# ExternalIO.net
KiCad netlist of a schematic drawn in Altium Designer
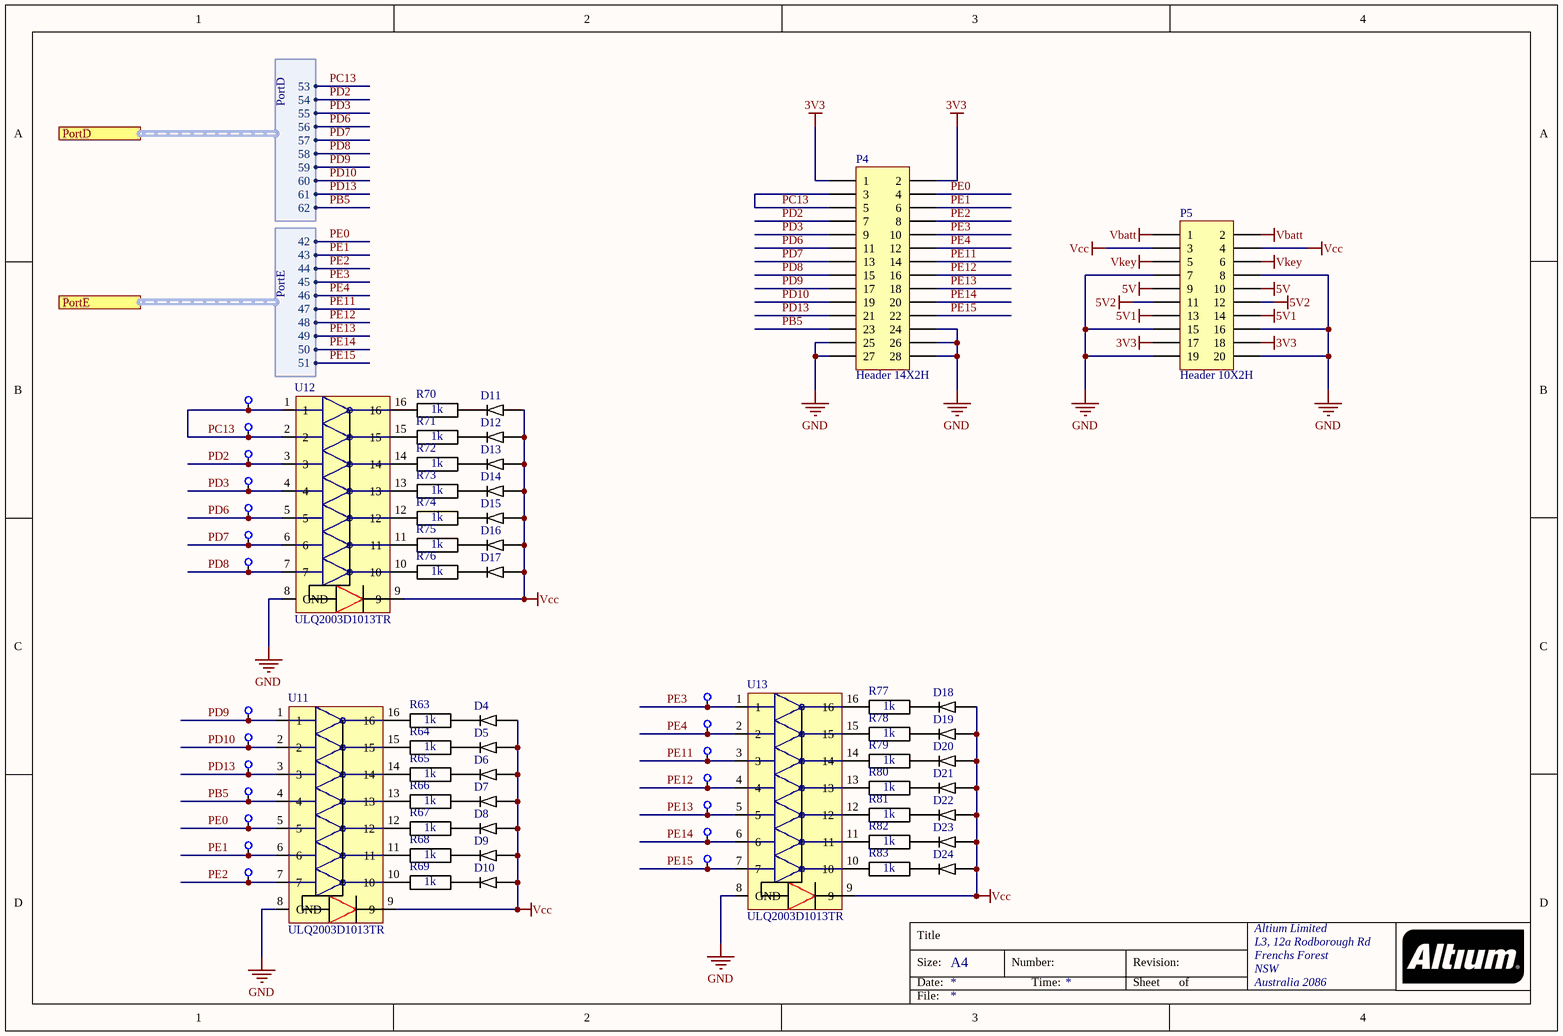
[diagram p0: ExternalIO.SchDoc]

(export (version "E")
  (design (tool "Eeschema 10.0.6"))
  (components
    (comp (ref "D4")
      (value "LED")
      (footprint "LED 0805")
      (description "LTST-C171GKT")
      (libsource (lib "Maks_lib") (part "LED"))
    )
    (comp (ref "D5")
      (value "LED")
      (footprint "LED 0805")
      (description "LTST-C171GKT")
      (libsource (lib "Maks_lib") (part "LED"))
    )
    (comp (ref "D6")
      (value "LED")
      (footprint "LED 0805")
      (description "LTST-C171GKT")
      (libsource (lib "Maks_lib") (part "LED"))
    )
    (comp (ref "D7")
      (value "LED")
      (footprint "LED 0805")
      (description "LTST-C171GKT")
      (libsource (lib "Maks_lib") (part "LED"))
    )
    (comp (ref "D8")
      (value "LED")
      (footprint "LED 0805")
      (description "LTST-C171GKT")
      (libsource (lib "Maks_lib") (part "LED"))
    )
    (comp (ref "D9")
      (value "LED")
      (footprint "LED 0805")
      (description "LTST-C171GKT")
      (libsource (lib "Maks_lib") (part "LED"))
    )
    (comp (ref "D10")
      (value "LED")
      (footprint "LED 0805")
      (description "LTST-C171GKT")
      (libsource (lib "Maks_lib") (part "LED"))
    )
    (comp (ref "D11")
      (value "LED")
      (footprint "LED 0805")
      (description "LTST-C171GKT")
      (libsource (lib "Maks_lib") (part "LED"))
    )
    (comp (ref "D12")
      (value "LED")
      (footprint "LED 0805")
      (description "LTST-C171GKT")
      (libsource (lib "Maks_lib") (part "LED"))
    )
    (comp (ref "D13")
      (value "LED")
      (footprint "LED 0805")
      (description "LTST-C171GKT")
      (libsource (lib "Maks_lib") (part "LED"))
    )
    (comp (ref "D14")
      (value "LED")
      (footprint "LED 0805")
      (description "LTST-C171GKT")
      (libsource (lib "Maks_lib") (part "LED"))
    )
    (comp (ref "D15")
      (value "LED")
      (footprint "LED 0805")
      (description "LTST-C171GKT")
      (libsource (lib "Maks_lib") (part "LED"))
    )
    (comp (ref "D16")
      (value "LED")
      (footprint "LED 0805")
      (description "LTST-C171GKT")
      (libsource (lib "Maks_lib") (part "LED"))
    )
    (comp (ref "D17")
      (value "LED")
      (footprint "LED 0805")
      (description "LTST-C171GKT")
      (libsource (lib "Maks_lib") (part "LED"))
    )
    (comp (ref "D18")
      (value "LED")
      (footprint "LED 0805")
      (description "LTST-C171GKT")
      (libsource (lib "Maks_lib") (part "LED"))
    )
    (comp (ref "D19")
      (value "LED")
      (footprint "LED 0805")
      (description "LTST-C171GKT")
      (libsource (lib "Maks_lib") (part "LED"))
    )
    (comp (ref "D20")
      (value "LED")
      (footprint "LED 0805")
      (description "LTST-C171GKT")
      (libsource (lib "Maks_lib") (part "LED"))
    )
    (comp (ref "D21")
      (value "LED")
      (footprint "LED 0805")
      (description "LTST-C171GKT")
      (libsource (lib "Maks_lib") (part "LED"))
    )
    (comp (ref "D22")
      (value "LED")
      (footprint "LED 0805")
      (description "LTST-C171GKT")
      (libsource (lib "Maks_lib") (part "LED"))
    )
    (comp (ref "D23")
      (value "LED")
      (footprint "LED 0805")
      (description "LTST-C171GKT")
      (libsource (lib "Maks_lib") (part "LED"))
    )
    (comp (ref "D24")
      (value "LED")
      (footprint "LED 0805")
      (description "LTST-C171GKT")
      (libsource (lib "Maks_lib") (part "LED"))
    )
    (comp (ref "P4")
      (value "Header 14X2H")
      (footprint "HDR2X14H")
      (description "Header, 14-Pin, Dual row, Right Angle")
      (fields (field (name "PUBLISHER") "Altium Limited"))
      (libsource (lib "Miscellaneous Connectors") (part "Header 14X2H"))
    )
    (comp (ref "P5")
      (value "Header 10X2H")
      (footprint "HDR2X10H")
      (description "Header, 10-Pin, Dual row, Right Angle")
      (fields (field (name "PUBLISHER") "Altium Limited"))
      (libsource (lib "Miscellaneous Connectors") (part "Header 10X2H"))
    )
    (comp (ref "R63")
      (value "1k")
      (footprint "SMD 0805")
      (description "RC0805FR-071KL")
      (libsource (lib "Maks_lib") (part "Resistor"))
    )
    (comp (ref "R64")
      (value "1k")
      (footprint "SMD 0805")
      (description "RC0805FR-071KL")
      (libsource (lib "Maks_lib") (part "Resistor"))
    )
    (comp (ref "R65")
      (value "1k")
      (footprint "SMD 0805")
      (description "RC0805FR-071KL")
      (libsource (lib "Maks_lib") (part "Resistor"))
    )
    (comp (ref "R66")
      (value "1k")
      (footprint "SMD 0805")
      (description "RC0805FR-071KL")
      (libsource (lib "Maks_lib") (part "Resistor"))
    )
    (comp (ref "R67")
      (value "1k")
      (footprint "SMD 0805")
      (description "RC0805FR-071KL")
      (libsource (lib "Maks_lib") (part "Resistor"))
    )
    (comp (ref "R68")
      (value "1k")
      (footprint "SMD 0805")
      (description "RC0805FR-071KL")
      (libsource (lib "Maks_lib") (part "Resistor"))
    )
    (comp (ref "R69")
      (value "1k")
      (footprint "SMD 0805")
      (description "RC0805FR-071KL")
      (libsource (lib "Maks_lib") (part "Resistor"))
    )
    (comp (ref "R70")
      (value "1k")
      (footprint "SMD 0805")
      (description "RC0805FR-071KL")
      (libsource (lib "Maks_lib") (part "Resistor"))
    )
    (comp (ref "R71")
      (value "1k")
      (footprint "SMD 0805")
      (description "RC0805FR-071KL")
      (libsource (lib "Maks_lib") (part "Resistor"))
    )
    (comp (ref "R72")
      (value "1k")
      (footprint "SMD 0805")
      (description "RC0805FR-071KL")
      (libsource (lib "Maks_lib") (part "Resistor"))
    )
    (comp (ref "R73")
      (value "1k")
      (footprint "SMD 0805")
      (description "RC0805FR-071KL")
      (libsource (lib "Maks_lib") (part "Resistor"))
    )
    (comp (ref "R74")
      (value "1k")
      (footprint "SMD 0805")
      (description "RC0805FR-071KL")
      (libsource (lib "Maks_lib") (part "Resistor"))
    )
    (comp (ref "R75")
      (value "1k")
      (footprint "SMD 0805")
      (description "RC0805FR-071KL")
      (libsource (lib "Maks_lib") (part "Resistor"))
    )
    (comp (ref "R76")
      (value "1k")
      (footprint "SMD 0805")
      (description "RC0805FR-071KL")
      (libsource (lib "Maks_lib") (part "Resistor"))
    )
    (comp (ref "R77")
      (value "1k")
      (footprint "SMD 0805")
      (description "RC0805FR-071KL")
      (libsource (lib "Maks_lib") (part "Resistor"))
    )
    (comp (ref "R78")
      (value "1k")
      (footprint "SMD 0805")
      (description "RC0805FR-071KL")
      (libsource (lib "Maks_lib") (part "Resistor"))
    )
    (comp (ref "R79")
      (value "1k")
      (footprint "SMD 0805")
      (description "RC0805FR-071KL")
      (libsource (lib "Maks_lib") (part "Resistor"))
    )
    (comp (ref "R80")
      (value "1k")
      (footprint "SMD 0805")
      (description "RC0805FR-071KL")
      (libsource (lib "Maks_lib") (part "Resistor"))
    )
    (comp (ref "R81")
      (value "1k")
      (footprint "SMD 0805")
      (description "RC0805FR-071KL")
      (libsource (lib "Maks_lib") (part "Resistor"))
    )
    (comp (ref "R82")
      (value "1k")
      (footprint "SMD 0805")
      (description "RC0805FR-071KL")
      (libsource (lib "Maks_lib") (part "Resistor"))
    )
    (comp (ref "R83")
      (value "1k")
      (footprint "SMD 0805")
      (description "RC0805FR-071KL")
      (libsource (lib "Maks_lib") (part "Resistor"))
    )
    (comp (ref "TP69")
      (value "TestPoint")
      (footprint "TESTPOINT")
      (description "testPoint")
      (libsource (lib "Maks_lib") (part "TestPoint"))
    )
    (comp (ref "TP70")
      (value "TestPoint")
      (footprint "TESTPOINT")
      (description "testPoint")
      (libsource (lib "Maks_lib") (part "TestPoint"))
    )
    (comp (ref "TP71")
      (value "TestPoint")
      (footprint "TESTPOINT")
      (description "testPoint")
      (libsource (lib "Maks_lib") (part "TestPoint"))
    )
    (comp (ref "TP72")
      (value "TestPoint")
      (footprint "TESTPOINT")
      (description "testPoint")
      (libsource (lib "Maks_lib") (part "TestPoint"))
    )
    (comp (ref "TP73")
      (value "TestPoint")
      (footprint "TESTPOINT")
      (description "testPoint")
      (libsource (lib "Maks_lib") (part "TestPoint"))
    )
    (comp (ref "TP74")
      (value "TestPoint")
      (footprint "TESTPOINT")
      (description "testPoint")
      (libsource (lib "Maks_lib") (part "TestPoint"))
    )
    (comp (ref "TP75")
      (value "TestPoint")
      (footprint "TESTPOINT")
      (description "testPoint")
      (libsource (lib "Maks_lib") (part "TestPoint"))
    )
    (comp (ref "TP76")
      (value "TestPoint")
      (footprint "TESTPOINT")
      (description "testPoint")
      (libsource (lib "Maks_lib") (part "TestPoint"))
    )
    (comp (ref "TP77")
      (value "TestPoint")
      (footprint "TESTPOINT")
      (description "testPoint")
      (libsource (lib "Maks_lib") (part "TestPoint"))
    )
    (comp (ref "TP78")
      (value "TestPoint")
      (footprint "TESTPOINT")
      (description "testPoint")
      (libsource (lib "Maks_lib") (part "TestPoint"))
    )
    (comp (ref "TP79")
      (value "TestPoint")
      (footprint "TESTPOINT")
      (description "testPoint")
      (libsource (lib "Maks_lib") (part "TestPoint"))
    )
    (comp (ref "TP80")
      (value "TestPoint")
      (footprint "TESTPOINT")
      (description "testPoint")
      (libsource (lib "Maks_lib") (part "TestPoint"))
    )
    (comp (ref "TP81")
      (value "TestPoint")
      (footprint "TESTPOINT")
      (description "testPoint")
      (libsource (lib "Maks_lib") (part "TestPoint"))
    )
    (comp (ref "TP82")
      (value "TestPoint")
      (footprint "TESTPOINT")
      (description "testPoint")
      (libsource (lib "Maks_lib") (part "TestPoint"))
    )
    (comp (ref "TP83")
      (value "TestPoint")
      (footprint "TESTPOINT")
      (description "testPoint")
      (libsource (lib "Maks_lib") (part "TestPoint"))
    )
    (comp (ref "TP84")
      (value "TestPoint")
      (footprint "TESTPOINT")
      (description "testPoint")
      (libsource (lib "Maks_lib") (part "TestPoint"))
    )
    (comp (ref "TP85")
      (value "TestPoint")
      (footprint "TESTPOINT")
      (description "testPoint")
      (libsource (lib "Maks_lib") (part "TestPoint"))
    )
    (comp (ref "TP86")
      (value "TestPoint")
      (footprint "TESTPOINT")
      (description "testPoint")
      (libsource (lib "Maks_lib") (part "TestPoint"))
    )
    (comp (ref "TP87")
      (value "TestPoint")
      (footprint "TESTPOINT")
      (description "testPoint")
      (libsource (lib "Maks_lib") (part "TestPoint"))
    )
    (comp (ref "TP88")
      (value "TestPoint")
      (footprint "TESTPOINT")
      (description "testPoint")
      (libsource (lib "Maks_lib") (part "TestPoint"))
    )
    (comp (ref "TP89")
      (value "TestPoint")
      (footprint "TESTPOINT")
      (description "testPoint")
      (libsource (lib "Maks_lib") (part "TestPoint"))
    )
    (comp (ref "U11")
      (value "ULQ2003D1013TR")
      (footprint "SOIC127P600X175_HS-17M")
      (libsource (lib "Maks_lib") (part "ULN2003AIDR"))
    )
    (comp (ref "U12")
      (value "ULQ2003D1013TR")
      (footprint "SOIC127P600X175_HS-17M")
      (libsource (lib "Maks_lib") (part "ULN2003AIDR"))
    )
    (comp (ref "U13")
      (value "ULQ2003D1013TR")
      (footprint "SOIC127P600X175_HS-17M")
      (libsource (lib "Maks_lib") (part "ULN2003AIDR"))
    )
  )
  (nets
    (net (code "3") (name "/PB5") (class "Default")
      (node (ref "P4") (pin "23") (pinfunction "23_23") (pintype "passive"))
      (node (ref "TP79") (pin "0") (pinfunction "0_0") (pintype "passive"))
      (node (ref "U11") (pin "4") (pinfunction "4_4") (pintype "passive"))
    )
    (net (code "4") (name "/PC13") (class "Default")
      (node (ref "P4") (pin "3") (pinfunction "3_3") (pintype "passive"))
      (node (ref "P4") (pin "5") (pinfunction "5_5") (pintype "passive"))
      (node (ref "TP69") (pin "0") (pinfunction "0_0") (pintype "passive"))
      (node (ref "TP70") (pin "0") (pinfunction "0_0") (pintype "passive"))
      (node (ref "U12") (pin "1") (pinfunction "1_1") (pintype "passive"))
      (node (ref "U12") (pin "2") (pinfunction "2_2") (pintype "passive"))
    )
    (net (code "5") (name "/PD2") (class "Default")
      (node (ref "P4") (pin "7") (pinfunction "7_7") (pintype "passive"))
      (node (ref "TP71") (pin "0") (pinfunction "0_0") (pintype "passive"))
      (node (ref "U12") (pin "3") (pinfunction "3_3") (pintype "passive"))
    )
    (net (code "6") (name "/PD3") (class "Default")
      (node (ref "P4") (pin "9") (pinfunction "9_9") (pintype "passive"))
      (node (ref "TP72") (pin "0") (pinfunction "0_0") (pintype "passive"))
      (node (ref "U12") (pin "4") (pinfunction "4_4") (pintype "passive"))
    )
    (net (code "7") (name "/PD6") (class "Default")
      (node (ref "P4") (pin "11") (pinfunction "11_11") (pintype "passive"))
      (node (ref "TP73") (pin "0") (pinfunction "0_0") (pintype "passive"))
      (node (ref "U12") (pin "5") (pinfunction "5_5") (pintype "passive"))
    )
    (net (code "8") (name "/PD7") (class "Default")
      (node (ref "P4") (pin "13") (pinfunction "13_13") (pintype "passive"))
      (node (ref "TP74") (pin "0") (pinfunction "0_0") (pintype "passive"))
      (node (ref "U12") (pin "6") (pinfunction "6_6") (pintype "passive"))
    )
    (net (code "9") (name "/PD8") (class "Default")
      (node (ref "P4") (pin "15") (pinfunction "15_15") (pintype "passive"))
      (node (ref "TP75") (pin "0") (pinfunction "0_0") (pintype "passive"))
      (node (ref "U12") (pin "7") (pinfunction "7_7") (pintype "passive"))
    )
    (net (code "10") (name "/PD9") (class "Default")
      (node (ref "P4") (pin "17") (pinfunction "17_17") (pintype "passive"))
      (node (ref "TP76") (pin "0") (pinfunction "0_0") (pintype "passive"))
      (node (ref "U11") (pin "1") (pinfunction "1_1") (pintype "passive"))
    )
    (net (code "11") (name "/PD10") (class "Default")
      (node (ref "P4") (pin "19") (pinfunction "19_19") (pintype "passive"))
      (node (ref "TP77") (pin "0") (pinfunction "0_0") (pintype "passive"))
      (node (ref "U11") (pin "2") (pinfunction "2_2") (pintype "passive"))
    )
    (net (code "12") (name "/PD13") (class "Default")
      (node (ref "P4") (pin "21") (pinfunction "21_21") (pintype "passive"))
      (node (ref "TP78") (pin "0") (pinfunction "0_0") (pintype "passive"))
      (node (ref "U11") (pin "3") (pinfunction "3_3") (pintype "passive"))
    )
    (net (code "13") (name "/PE0") (class "Default")
      (node (ref "P4") (pin "4") (pinfunction "4_4") (pintype "passive"))
      (node (ref "TP80") (pin "0") (pinfunction "0_0") (pintype "passive"))
      (node (ref "U11") (pin "5") (pinfunction "5_5") (pintype "passive"))
    )
    (net (code "14") (name "/PE1") (class "Default")
      (node (ref "P4") (pin "6") (pinfunction "6_6") (pintype "passive"))
      (node (ref "TP81") (pin "0") (pinfunction "0_0") (pintype "passive"))
      (node (ref "U11") (pin "6") (pinfunction "6_6") (pintype "passive"))
    )
    (net (code "15") (name "/PE2") (class "Default")
      (node (ref "P4") (pin "8") (pinfunction "8_8") (pintype "passive"))
      (node (ref "TP82") (pin "0") (pinfunction "0_0") (pintype "passive"))
      (node (ref "U11") (pin "7") (pinfunction "7_7") (pintype "passive"))
    )
    (net (code "16") (name "/PE3") (class "Default")
      (node (ref "P4") (pin "10") (pinfunction "10_10") (pintype "passive"))
      (node (ref "TP83") (pin "0") (pinfunction "0_0") (pintype "passive"))
      (node (ref "U13") (pin "1") (pinfunction "1_1") (pintype "passive"))
    )
    (net (code "17") (name "/PE4") (class "Default")
      (node (ref "P4") (pin "12") (pinfunction "12_12") (pintype "passive"))
      (node (ref "TP84") (pin "0") (pinfunction "0_0") (pintype "passive"))
      (node (ref "U13") (pin "2") (pinfunction "2_2") (pintype "passive"))
    )
    (net (code "18") (name "/PE11") (class "Default")
      (node (ref "P4") (pin "14") (pinfunction "14_14") (pintype "passive"))
      (node (ref "TP85") (pin "0") (pinfunction "0_0") (pintype "passive"))
      (node (ref "U13") (pin "3") (pinfunction "3_3") (pintype "passive"))
    )
    (net (code "19") (name "/PE12") (class "Default")
      (node (ref "P4") (pin "16") (pinfunction "16_16") (pintype "passive"))
      (node (ref "TP86") (pin "0") (pinfunction "0_0") (pintype "passive"))
      (node (ref "U13") (pin "4") (pinfunction "4_4") (pintype "passive"))
    )
    (net (code "20") (name "/PE13") (class "Default")
      (node (ref "P4") (pin "18") (pinfunction "18_18") (pintype "passive"))
      (node (ref "TP87") (pin "0") (pinfunction "0_0") (pintype "passive"))
      (node (ref "U13") (pin "5") (pinfunction "5_5") (pintype "passive"))
    )
    (net (code "21") (name "/PE14") (class "Default")
      (node (ref "P4") (pin "20") (pinfunction "20_20") (pintype "passive"))
      (node (ref "TP88") (pin "0") (pinfunction "0_0") (pintype "passive"))
      (node (ref "U13") (pin "6") (pinfunction "6_6") (pintype "passive"))
    )
    (net (code "22") (name "/PE15") (class "Default")
      (node (ref "P4") (pin "22") (pinfunction "22_22") (pintype "passive"))
      (node (ref "TP89") (pin "0") (pinfunction "0_0") (pintype "passive"))
      (node (ref "U13") (pin "7") (pinfunction "7_7") (pintype "passive"))
    )
    (net (code "25") (name "3V3") (class "Default")
      (node (ref "P4") (pin "1") (pinfunction "1_1") (pintype "passive"))
      (node (ref "P4") (pin "2") (pinfunction "2_2") (pintype "passive"))
      (node (ref "P5") (pin "17") (pinfunction "17_17") (pintype "passive"))
      (node (ref "P5") (pin "18") (pinfunction "18_18") (pintype "passive"))
    )
    (net (code "26") (name "5V") (class "Default")
      (node (ref "P5") (pin "10") (pinfunction "10_10") (pintype "passive"))
      (node (ref "P5") (pin "9") (pinfunction "9_9") (pintype "passive"))
    )
    (net (code "27") (name "5V1") (class "Default")
      (node (ref "P5") (pin "13") (pinfunction "13_13") (pintype "passive"))
      (node (ref "P5") (pin "14") (pinfunction "14_14") (pintype "passive"))
    )
    (net (code "28") (name "5V2") (class "Default")
      (node (ref "P5") (pin "11") (pinfunction "11_11") (pintype "passive"))
      (node (ref "P5") (pin "12") (pinfunction "12_12") (pintype "passive"))
    )
    (net (code "29") (name "GND") (class "Default")
      (node (ref "P4") (pin "24") (pinfunction "24_24") (pintype "passive"))
      (node (ref "P4") (pin "25") (pinfunction "25_25") (pintype "passive"))
      (node (ref "P4") (pin "26") (pinfunction "26_26") (pintype "passive"))
      (node (ref "P4") (pin "27") (pinfunction "27_27") (pintype "passive"))
      (node (ref "P4") (pin "28") (pinfunction "28_28") (pintype "passive"))
      (node (ref "P5") (pin "15") (pinfunction "15_15") (pintype "passive"))
      (node (ref "P5") (pin "16") (pinfunction "16_16") (pintype "passive"))
      (node (ref "P5") (pin "19") (pinfunction "19_19") (pintype "passive"))
      (node (ref "P5") (pin "20") (pinfunction "20_20") (pintype "passive"))
      (node (ref "P5") (pin "7") (pinfunction "7_7") (pintype "passive"))
      (node (ref "P5") (pin "8") (pinfunction "8_8") (pintype "passive"))
      (node (ref "U11") (pin "8") (pinfunction "GND_8") (pintype "passive"))
      (node (ref "U12") (pin "8") (pinfunction "GND_8") (pintype "passive"))
      (node (ref "U13") (pin "8") (pinfunction "GND_8") (pintype "passive"))
    )
    (net (code "30") (name "Net-(D4-Pad-)") (class "Default")
      (node (ref "D4") (pin "-") (pinfunction "-_-") (pintype "passive"))
      (node (ref "R63") (pin "2") (pinfunction "2_2") (pintype "passive"))
    )
    (net (code "31") (name "Net-(D5-Pad-)") (class "Default")
      (node (ref "D5") (pin "-") (pinfunction "-_-") (pintype "passive"))
      (node (ref "R64") (pin "2") (pinfunction "2_2") (pintype "passive"))
    )
    (net (code "32") (name "Net-(D6-Pad-)") (class "Default")
      (node (ref "D6") (pin "-") (pinfunction "-_-") (pintype "passive"))
      (node (ref "R65") (pin "2") (pinfunction "2_2") (pintype "passive"))
    )
    (net (code "33") (name "Net-(D7-Pad-)") (class "Default")
      (node (ref "D7") (pin "-") (pinfunction "-_-") (pintype "passive"))
      (node (ref "R66") (pin "2") (pinfunction "2_2") (pintype "passive"))
    )
    (net (code "34") (name "Net-(D8-Pad-)") (class "Default")
      (node (ref "D8") (pin "-") (pinfunction "-_-") (pintype "passive"))
      (node (ref "R67") (pin "2") (pinfunction "2_2") (pintype "passive"))
    )
    (net (code "35") (name "Net-(D9-Pad-)") (class "Default")
      (node (ref "D9") (pin "-") (pinfunction "-_-") (pintype "passive"))
      (node (ref "R68") (pin "2") (pinfunction "2_2") (pintype "passive"))
    )
    (net (code "36") (name "Net-(D10-Pad-)") (class "Default")
      (node (ref "D10") (pin "-") (pinfunction "-_-") (pintype "passive"))
      (node (ref "R69") (pin "2") (pinfunction "2_2") (pintype "passive"))
    )
    (net (code "37") (name "Net-(D11-Pad-)") (class "Default")
      (node (ref "D11") (pin "-") (pinfunction "-_-") (pintype "passive"))
      (node (ref "R70") (pin "2") (pinfunction "2_2") (pintype "passive"))
    )
    (net (code "38") (name "Net-(D12-Pad-)") (class "Default")
      (node (ref "D12") (pin "-") (pinfunction "-_-") (pintype "passive"))
      (node (ref "R71") (pin "2") (pinfunction "2_2") (pintype "passive"))
    )
    (net (code "39") (name "Net-(D13-Pad-)") (class "Default")
      (node (ref "D13") (pin "-") (pinfunction "-_-") (pintype "passive"))
      (node (ref "R72") (pin "2") (pinfunction "2_2") (pintype "passive"))
    )
    (net (code "40") (name "Net-(D14-Pad-)") (class "Default")
      (node (ref "D14") (pin "-") (pinfunction "-_-") (pintype "passive"))
      (node (ref "R73") (pin "2") (pinfunction "2_2") (pintype "passive"))
    )
    (net (code "41") (name "Net-(D15-Pad-)") (class "Default")
      (node (ref "D15") (pin "-") (pinfunction "-_-") (pintype "passive"))
      (node (ref "R74") (pin "2") (pinfunction "2_2") (pintype "passive"))
    )
    (net (code "42") (name "Net-(D16-Pad-)") (class "Default")
      (node (ref "D16") (pin "-") (pinfunction "-_-") (pintype "passive"))
      (node (ref "R75") (pin "2") (pinfunction "2_2") (pintype "passive"))
    )
    (net (code "43") (name "Net-(D17-Pad-)") (class "Default")
      (node (ref "D17") (pin "-") (pinfunction "-_-") (pintype "passive"))
      (node (ref "R76") (pin "2") (pinfunction "2_2") (pintype "passive"))
    )
    (net (code "44") (name "Net-(D18-Pad-)") (class "Default")
      (node (ref "D18") (pin "-") (pinfunction "-_-") (pintype "passive"))
      (node (ref "R77") (pin "2") (pinfunction "2_2") (pintype "passive"))
    )
    (net (code "45") (name "Net-(D19-Pad-)") (class "Default")
      (node (ref "D19") (pin "-") (pinfunction "-_-") (pintype "passive"))
      (node (ref "R78") (pin "2") (pinfunction "2_2") (pintype "passive"))
    )
    (net (code "46") (name "Net-(D20-Pad-)") (class "Default")
      (node (ref "D20") (pin "-") (pinfunction "-_-") (pintype "passive"))
      (node (ref "R79") (pin "2") (pinfunction "2_2") (pintype "passive"))
    )
    (net (code "47") (name "Net-(D21-Pad-)") (class "Default")
      (node (ref "D21") (pin "-") (pinfunction "-_-") (pintype "passive"))
      (node (ref "R80") (pin "2") (pinfunction "2_2") (pintype "passive"))
    )
    (net (code "48") (name "Net-(D22-Pad-)") (class "Default")
      (node (ref "D22") (pin "-") (pinfunction "-_-") (pintype "passive"))
      (node (ref "R81") (pin "2") (pinfunction "2_2") (pintype "passive"))
    )
    (net (code "49") (name "Net-(D23-Pad-)") (class "Default")
      (node (ref "D23") (pin "-") (pinfunction "-_-") (pintype "passive"))
      (node (ref "R82") (pin "2") (pinfunction "2_2") (pintype "passive"))
    )
    (net (code "50") (name "Net-(D24-Pad-)") (class "Default")
      (node (ref "D24") (pin "-") (pinfunction "-_-") (pintype "passive"))
      (node (ref "R83") (pin "2") (pinfunction "2_2") (pintype "passive"))
    )
    (net (code "51") (name "Net-(R63-Pad1)") (class "Default")
      (node (ref "R63") (pin "1") (pinfunction "1_1") (pintype "passive"))
      (node (ref "U11") (pin "16") (pinfunction "16_16") (pintype "passive"))
    )
    (net (code "52") (name "Net-(R64-Pad1)") (class "Default")
      (node (ref "R64") (pin "1") (pinfunction "1_1") (pintype "passive"))
      (node (ref "U11") (pin "15") (pinfunction "15_15") (pintype "passive"))
    )
    (net (code "53") (name "Net-(R65-Pad1)") (class "Default")
      (node (ref "R65") (pin "1") (pinfunction "1_1") (pintype "passive"))
      (node (ref "U11") (pin "14") (pinfunction "14_14") (pintype "passive"))
    )
    (net (code "54") (name "Net-(R66-Pad1)") (class "Default")
      (node (ref "R66") (pin "1") (pinfunction "1_1") (pintype "passive"))
      (node (ref "U11") (pin "13") (pinfunction "13_13") (pintype "passive"))
    )
    (net (code "55") (name "Net-(R67-Pad1)") (class "Default")
      (node (ref "R67") (pin "1") (pinfunction "1_1") (pintype "passive"))
      (node (ref "U11") (pin "12") (pinfunction "12_12") (pintype "passive"))
    )
    (net (code "56") (name "Net-(R68-Pad1)") (class "Default")
      (node (ref "R68") (pin "1") (pinfunction "1_1") (pintype "passive"))
      (node (ref "U11") (pin "11") (pinfunction "11_11") (pintype "passive"))
    )
    (net (code "57") (name "Net-(R69-Pad1)") (class "Default")
      (node (ref "R69") (pin "1") (pinfunction "1_1") (pintype "passive"))
      (node (ref "U11") (pin "10") (pinfunction "10_10") (pintype "passive"))
    )
    (net (code "58") (name "Net-(R70-Pad1)") (class "Default")
      (node (ref "R70") (pin "1") (pinfunction "1_1") (pintype "passive"))
      (node (ref "U12") (pin "16") (pinfunction "16_16") (pintype "passive"))
    )
    (net (code "59") (name "Net-(R71-Pad1)") (class "Default")
      (node (ref "R71") (pin "1") (pinfunction "1_1") (pintype "passive"))
      (node (ref "U12") (pin "15") (pinfunction "15_15") (pintype "passive"))
    )
    (net (code "60") (name "Net-(R72-Pad1)") (class "Default")
      (node (ref "R72") (pin "1") (pinfunction "1_1") (pintype "passive"))
      (node (ref "U12") (pin "14") (pinfunction "14_14") (pintype "passive"))
    )
    (net (code "61") (name "Net-(R73-Pad1)") (class "Default")
      (node (ref "R73") (pin "1") (pinfunction "1_1") (pintype "passive"))
      (node (ref "U12") (pin "13") (pinfunction "13_13") (pintype "passive"))
    )
    (net (code "62") (name "Net-(R74-Pad1)") (class "Default")
      (node (ref "R74") (pin "1") (pinfunction "1_1") (pintype "passive"))
      (node (ref "U12") (pin "12") (pinfunction "12_12") (pintype "passive"))
    )
    (net (code "63") (name "Net-(R75-Pad1)") (class "Default")
      (node (ref "R75") (pin "1") (pinfunction "1_1") (pintype "passive"))
      (node (ref "U12") (pin "11") (pinfunction "11_11") (pintype "passive"))
    )
    (net (code "64") (name "Net-(R76-Pad1)") (class "Default")
      (node (ref "R76") (pin "1") (pinfunction "1_1") (pintype "passive"))
      (node (ref "U12") (pin "10") (pinfunction "10_10") (pintype "passive"))
    )
    (net (code "65") (name "Net-(R77-Pad1)") (class "Default")
      (node (ref "R77") (pin "1") (pinfunction "1_1") (pintype "passive"))
      (node (ref "U13") (pin "16") (pinfunction "16_16") (pintype "passive"))
    )
    (net (code "66") (name "Net-(R78-Pad1)") (class "Default")
      (node (ref "R78") (pin "1") (pinfunction "1_1") (pintype "passive"))
      (node (ref "U13") (pin "15") (pinfunction "15_15") (pintype "passive"))
    )
    (net (code "67") (name "Net-(R79-Pad1)") (class "Default")
      (node (ref "R79") (pin "1") (pinfunction "1_1") (pintype "passive"))
      (node (ref "U13") (pin "14") (pinfunction "14_14") (pintype "passive"))
    )
    (net (code "68") (name "Net-(R80-Pad1)") (class "Default")
      (node (ref "R80") (pin "1") (pinfunction "1_1") (pintype "passive"))
      (node (ref "U13") (pin "13") (pinfunction "13_13") (pintype "passive"))
    )
    (net (code "69") (name "Net-(R81-Pad1)") (class "Default")
      (node (ref "R81") (pin "1") (pinfunction "1_1") (pintype "passive"))
      (node (ref "U13") (pin "12") (pinfunction "12_12") (pintype "passive"))
    )
    (net (code "70") (name "Net-(R82-Pad1)") (class "Default")
      (node (ref "R82") (pin "1") (pinfunction "1_1") (pintype "passive"))
      (node (ref "U13") (pin "11") (pinfunction "11_11") (pintype "passive"))
    )
    (net (code "71") (name "Net-(R83-Pad1)") (class "Default")
      (node (ref "R83") (pin "1") (pinfunction "1_1") (pintype "passive"))
      (node (ref "U13") (pin "10") (pinfunction "10_10") (pintype "passive"))
    )
    (net (code "72") (name "Vbatt") (class "Default")
      (node (ref "P5") (pin "1") (pinfunction "1_1") (pintype "passive"))
      (node (ref "P5") (pin "2") (pinfunction "2_2") (pintype "passive"))
    )
    (net (code "73") (name "Vcc") (class "Default")
      (node (ref "D10") (pin "+") (pinfunction "+_+") (pintype "passive"))
      (node (ref "D11") (pin "+") (pinfunction "+_+") (pintype "passive"))
      (node (ref "D12") (pin "+") (pinfunction "+_+") (pintype "passive"))
      (node (ref "D13") (pin "+") (pinfunction "+_+") (pintype "passive"))
      (node (ref "D14") (pin "+") (pinfunction "+_+") (pintype "passive"))
      (node (ref "D15") (pin "+") (pinfunction "+_+") (pintype "passive"))
      (node (ref "D16") (pin "+") (pinfunction "+_+") (pintype "passive"))
      (node (ref "D17") (pin "+") (pinfunction "+_+") (pintype "passive"))
      (node (ref "D18") (pin "+") (pinfunction "+_+") (pintype "passive"))
      (node (ref "D19") (pin "+") (pinfunction "+_+") (pintype "passive"))
      (node (ref "D20") (pin "+") (pinfunction "+_+") (pintype "passive"))
      (node (ref "D21") (pin "+") (pinfunction "+_+") (pintype "passive"))
      (node (ref "D22") (pin "+") (pinfunction "+_+") (pintype "passive"))
      (node (ref "D23") (pin "+") (pinfunction "+_+") (pintype "passive"))
      (node (ref "D24") (pin "+") (pinfunction "+_+") (pintype "passive"))
      (node (ref "D4") (pin "+") (pinfunction "+_+") (pintype "passive"))
      (node (ref "D5") (pin "+") (pinfunction "+_+") (pintype "passive"))
      (node (ref "D6") (pin "+") (pinfunction "+_+") (pintype "passive"))
      (node (ref "D7") (pin "+") (pinfunction "+_+") (pintype "passive"))
      (node (ref "D8") (pin "+") (pinfunction "+_+") (pintype "passive"))
      (node (ref "D9") (pin "+") (pinfunction "+_+") (pintype "passive"))
      (node (ref "P5") (pin "3") (pinfunction "3_3") (pintype "passive"))
      (node (ref "P5") (pin "4") (pinfunction "4_4") (pintype "passive"))
      (node (ref "U11") (pin "9") (pinfunction "9_9") (pintype "passive"))
      (node (ref "U12") (pin "9") (pinfunction "9_9") (pintype "passive"))
      (node (ref "U13") (pin "9") (pinfunction "9_9") (pintype "passive"))
    )
    (net (code "74") (name "Vkey") (class "Default")
      (node (ref "P5") (pin "5") (pinfunction "5_5") (pintype "passive"))
      (node (ref "P5") (pin "6") (pinfunction "6_6") (pintype "passive"))
    )
  )
)
